# Controller_Rev_3.net
KiCad netlist of a schematic drawn in EAGLE
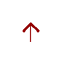
[diagram p0: schematic, sheet 1, part 1 of 3]
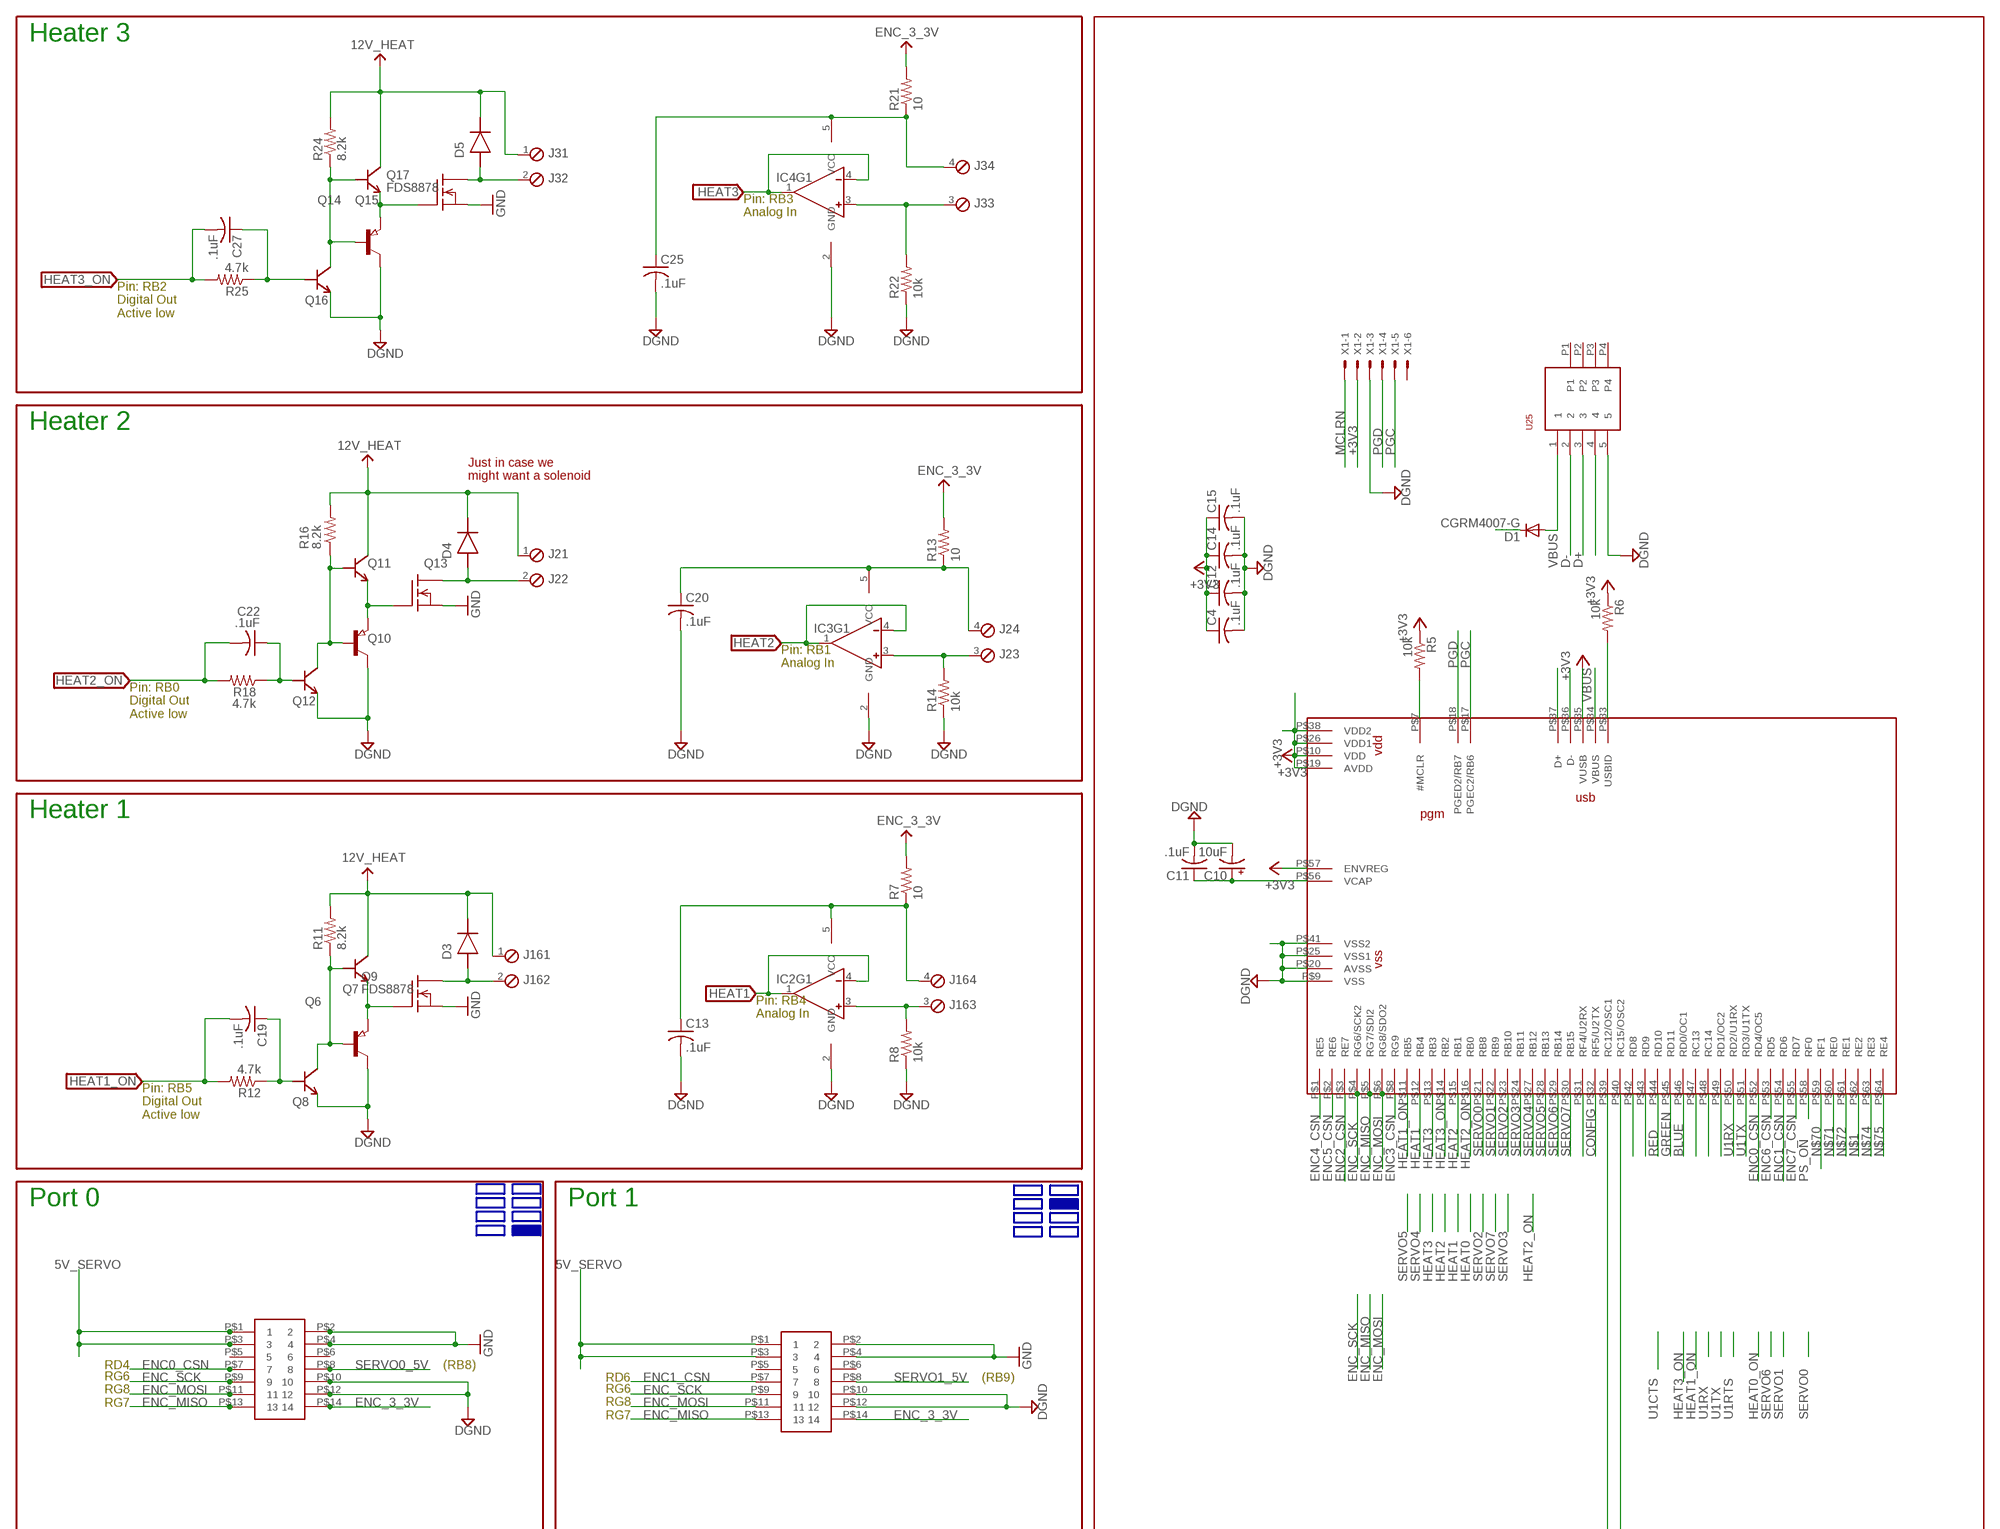
[diagram p1: schematic, sheet 1, part 2 of 3]
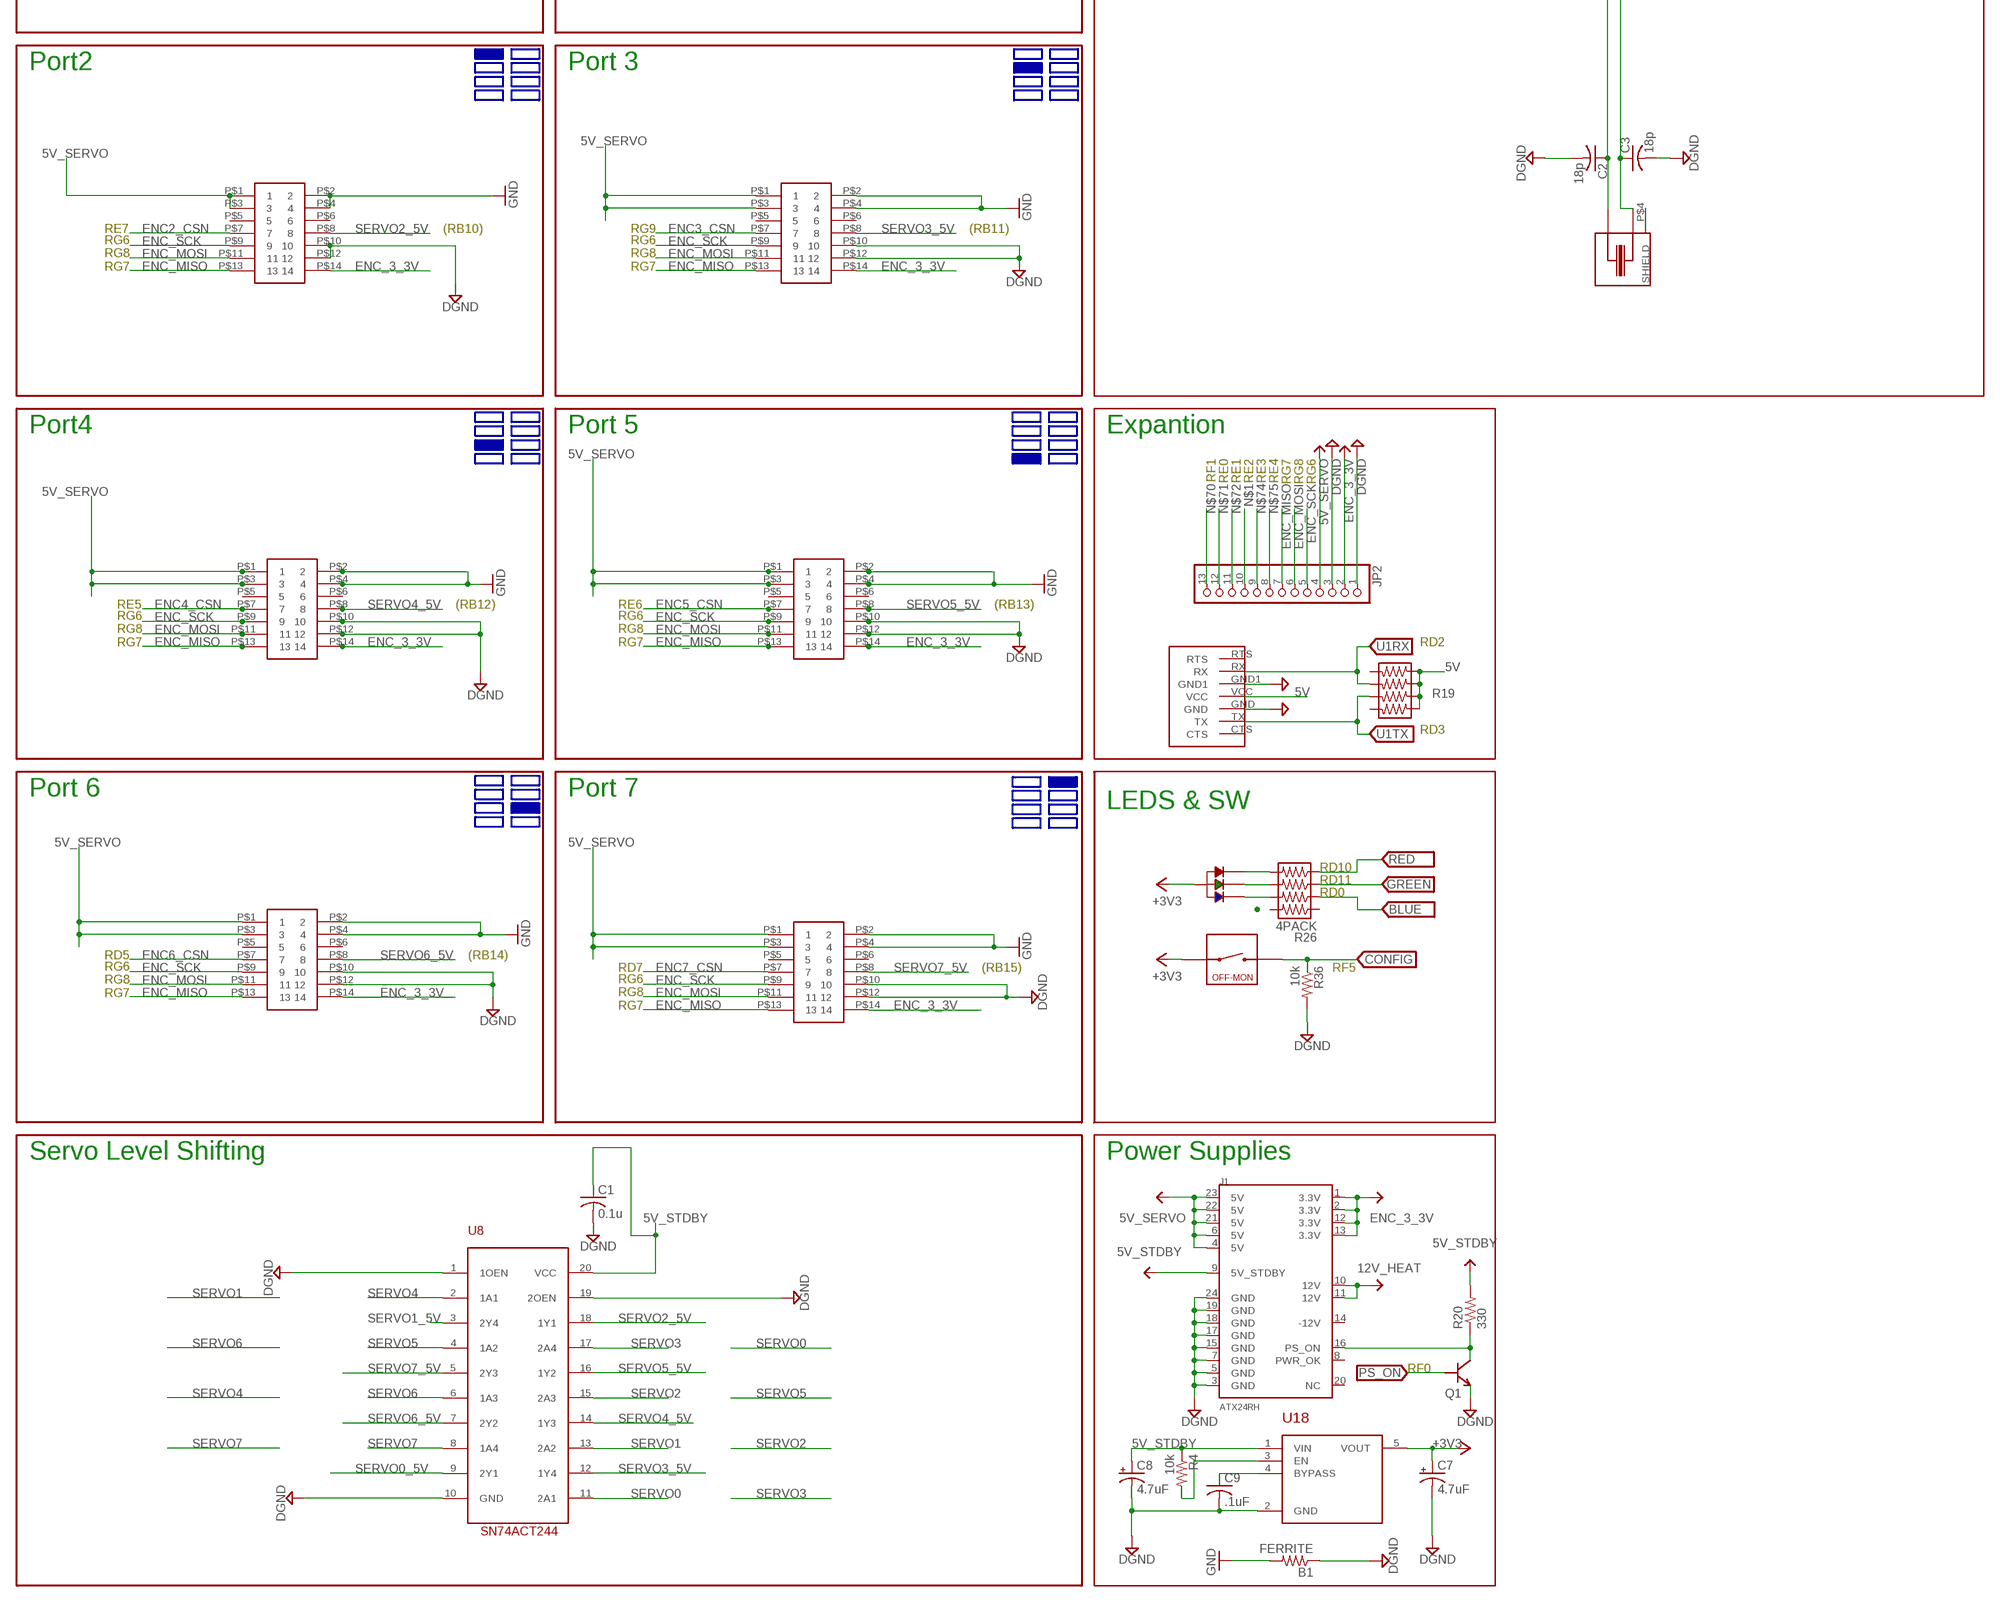
[diagram p2: schematic, sheet 1, part 3 of 3]

(export (version "E")
  (design (tool "Eeschema 10.0.6"))
  (components
    (comp (ref "B1")
      (value "FERRITE")
      (footprint "eagle-import:R0603")
      (libsource (lib "eagle-import") (part "R-US_R0603"))
    )
    (comp (ref "C1")
      (value "0.1u")
      (footprint "eagle-import:C0402")
      (libsource (lib "eagle-import") (part "resistor_C-USC0402"))
    )
    (comp (ref "C2")
      (value "18p")
      (footprint "eagle-import:C0603")
      (libsource (lib "eagle-import") (part "C-USC0603"))
    )
    (comp (ref "C3")
      (value "18p")
      (footprint "eagle-import:C0603")
      (libsource (lib "eagle-import") (part "C-USC0603"))
    )
    (comp (ref "C4")
      (value ".1uF")
      (footprint "eagle-import:C0603")
      (libsource (lib "eagle-import") (part "C-USC0603"))
    )
    (comp (ref "C7")
      (value "4.7uF")
      (footprint "eagle-import:R_2012-12R")
      (libsource (lib "eagle-import") (part "CPOL-USR/2012-12R"))
    )
    (comp (ref "C8")
      (value "4.7uF")
      (footprint "eagle-import:R_2012-12R")
      (libsource (lib "eagle-import") (part "CPOL-USR/2012-12R"))
    )
    (comp (ref "C9")
      (value ".1uF")
      (footprint "eagle-import:C0402")
      (libsource (lib "eagle-import") (part "C-USC0402"))
    )
    (comp (ref "C10")
      (value "10uF")
      (footprint "eagle-import:R_2012-12R")
      (libsource (lib "eagle-import") (part "CPOL-USR/2012-12R"))
    )
    (comp (ref "C11")
      (value ".1uF")
      (footprint "eagle-import:C0603")
      (libsource (lib "eagle-import") (part "C-USC0603"))
    )
    (comp (ref "C12")
      (value ".1uF")
      (footprint "eagle-import:C0603")
      (libsource (lib "eagle-import") (part "C-USC0603"))
    )
    (comp (ref "C13")
      (value ".1uF")
      (footprint "eagle-import:C0603")
      (libsource (lib "eagle-import") (part "C-USC0603"))
    )
    (comp (ref "C14")
      (value ".1uF")
      (footprint "eagle-import:C0603")
      (libsource (lib "eagle-import") (part "C-USC0603"))
    )
    (comp (ref "C15")
      (value ".1uF")
      (footprint "eagle-import:C0603")
      (libsource (lib "eagle-import") (part "C-USC0603"))
    )
    (comp (ref "C19")
      (value ".1uF")
      (footprint "eagle-import:C0603")
      (libsource (lib "eagle-import") (part "C-USC0603"))
    )
    (comp (ref "C20")
      (value ".1uF")
      (footprint "eagle-import:C0603")
      (libsource (lib "eagle-import") (part "C-USC0603"))
    )
    (comp (ref "C22")
      (value ".1uF")
      (footprint "eagle-import:C0603")
      (libsource (lib "eagle-import") (part "C-USC0603"))
    )
    (comp (ref "C25")
      (value ".1uF")
      (footprint "eagle-import:C0603")
      (libsource (lib "eagle-import") (part "C-USC0603"))
    )
    (comp (ref "C27")
      (value ".1uF")
      (footprint "eagle-import:C0603")
      (libsource (lib "eagle-import") (part "C-USC0603"))
    )
    (comp (ref "D1")
      (value "CGRM4007-G")
      (footprint "eagle-import:SOD-123_MINI-SMA")
      (libsource (lib "eagle-import") (part "CGRM400-G7"))
    )
    (comp (ref "D3")
      (value "DISCRETE_DIODESMA")
      (footprint "eagle-import:DISCRETE_SMA")
      (libsource (lib "eagle-import") (part "DISCRETE_DIODESMA"))
    )
    (comp (ref "D4")
      (value "DISCRETE_DIODESMA")
      (footprint "eagle-import:DISCRETE_SMA")
      (libsource (lib "eagle-import") (part "DISCRETE_DIODESMA"))
    )
    (comp (ref "D5")
      (value "DISCRETE_DIODESMA")
      (footprint "eagle-import:DISCRETE_SMA")
      (libsource (lib "eagle-import") (part "DISCRETE_DIODESMA"))
    )
    (comp (ref "IC2")
      (value "MICROCHIP_MCP6001-LT")
      (footprint "eagle-import:MICROCHIP_SC70-5-LT")
      (libsource (lib "eagle-import") (part "MICROCHIP_MCP6001-LT"))
    )
    (comp (ref "IC3")
      (value "MICROCHIP_MCP6001-LT")
      (footprint "eagle-import:MICROCHIP_SC70-5-LT")
      (libsource (lib "eagle-import") (part "MICROCHIP_MCP6001-LT"))
    )
    (comp (ref "IC4")
      (value "MICROCHIP_MCP6001-LT")
      (footprint "eagle-import:MICROCHIP_SC70-5-LT")
      (libsource (lib "eagle-import") (part "MICROCHIP_MCP6001-LT"))
    )
    (comp (ref "J1")
      (value "ATX24RH")
      (footprint "eagle-import:ATX24_RIGHT_ANGLE")
      (libsource (lib "eagle-import") (part "ATX24RH"))
    )
    (comp (ref "J2")
      (value "OSTVN04A150")
      (footprint "eagle-import:4POL254")
      (libsource (lib "eagle-import") (part "OSTVN04A150"))
    )
    (comp (ref "J3")
      (value "OSTVN04A150")
      (footprint "eagle-import:4POL254")
      (libsource (lib "eagle-import") (part "OSTVN04A150"))
    )
    (comp (ref "J10")
      (value "WASP7PIN")
      (footprint "eagle-import:WASP7PIN")
      (libsource (lib "eagle-import") (part "WASP7PIN"))
    )
    (comp (ref "J16")
      (value "OSTVN04A150")
      (footprint "eagle-import:4POL254")
      (libsource (lib "eagle-import") (part "OSTVN04A150"))
    )
    (comp (ref "JP2")
      (value "PINHD-1X13_BIG")
      (footprint "eagle-import:1X13-BIG")
      (libsource (lib "eagle-import") (part "PINHD-1X13_BIG"))
    )
    (comp (ref "Q1")
      (value "DISCRETE_MMBT3904LT1G")
      (footprint "eagle-import:DISCRETE_SOT23")
      (libsource (lib "eagle-import") (part "DISCRETE_MMBT3904LT1G"))
    )
    (comp (ref "Q6")
      (value "PNP-TRANSISTOR_SOT23")
      (footprint "eagle-import:SOT23")
      (libsource (lib "eagle-import") (part "PNP-TRANSISTOR_SOT23"))
    )
    (comp (ref "Q7")
      (value "DISCRETE_MMBT3904LT1G")
      (footprint "eagle-import:DISCRETE_SOT23")
      (libsource (lib "eagle-import") (part "DISCRETE_MMBT3904LT1G"))
    )
    (comp (ref "Q8")
      (value "DISCRETE_MMBT3904LT1G")
      (footprint "eagle-import:DISCRETE_SOT23")
      (libsource (lib "eagle-import") (part "DISCRETE_MMBT3904LT1G"))
    )
    (comp (ref "Q9")
      (value "FDS8878")
      (footprint "eagle-import:SO-8")
      (libsource (lib "eagle-import") (part "FDS5680"))
    )
    (comp (ref "Q10")
      (value "PNP-TRANSISTOR_SOT23")
      (footprint "eagle-import:SOT23")
      (libsource (lib "eagle-import") (part "PNP-TRANSISTOR_SOT23"))
    )
    (comp (ref "Q11")
      (value "DISCRETE_MMBT3904LT1G")
      (footprint "eagle-import:DISCRETE_SOT23")
      (libsource (lib "eagle-import") (part "DISCRETE_MMBT3904LT1G"))
    )
    (comp (ref "Q12")
      (value "DISCRETE_MMBT3904LT1G")
      (footprint "eagle-import:DISCRETE_SOT23")
      (libsource (lib "eagle-import") (part "DISCRETE_MMBT3904LT1G"))
    )
    (comp (ref "Q13")
      (value "FDS8878")
      (footprint "eagle-import:SO-8")
      (libsource (lib "eagle-import") (part "FDS5680"))
    )
    (comp (ref "Q14")
      (value "PNP-TRANSISTOR_SOT23")
      (footprint "eagle-import:SOT23")
      (libsource (lib "eagle-import") (part "PNP-TRANSISTOR_SOT23"))
    )
    (comp (ref "Q15")
      (value "DISCRETE_MMBT3904LT1G")
      (footprint "eagle-import:DISCRETE_SOT23")
      (libsource (lib "eagle-import") (part "DISCRETE_MMBT3904LT1G"))
    )
    (comp (ref "Q16")
      (value "DISCRETE_MMBT3904LT1G")
      (footprint "eagle-import:DISCRETE_SOT23")
      (libsource (lib "eagle-import") (part "DISCRETE_MMBT3904LT1G"))
    )
    (comp (ref "Q17")
      (value "FDS8878")
      (footprint "eagle-import:SO-8")
      (libsource (lib "eagle-import") (part "FDS5680"))
    )
    (comp (ref "R4")
      (value "10k")
      (footprint "eagle-import:R0402")
      (libsource (lib "eagle-import") (part "R-US_R0402"))
    )
    (comp (ref "R5")
      (value "10k")
      (footprint "eagle-import:R0603")
      (libsource (lib "eagle-import") (part "R-US_R0603"))
    )
    (comp (ref "R6")
      (value "10k")
      (footprint "eagle-import:R0603")
      (libsource (lib "eagle-import") (part "R-US_R0603"))
    )
    (comp (ref "R7")
      (value "10")
      (footprint "eagle-import:R0603")
      (libsource (lib "eagle-import") (part "R-US_R0603"))
    )
    (comp (ref "R8")
      (value "10k")
      (footprint "eagle-import:R0603")
      (libsource (lib "eagle-import") (part "R-US_R0603"))
    )
    (comp (ref "R11")
      (value "8.2k")
      (footprint "eagle-import:R0603")
      (libsource (lib "eagle-import") (part "R-US_R0603"))
    )
    (comp (ref "R12")
      (value "4.7k")
      (footprint "eagle-import:R0603")
      (libsource (lib "eagle-import") (part "R-US_R0603"))
    )
    (comp (ref "R13")
      (value "10")
      (footprint "eagle-import:R0603")
      (libsource (lib "eagle-import") (part "R-US_R0603"))
    )
    (comp (ref "R14")
      (value "10k")
      (footprint "eagle-import:R0603")
      (libsource (lib "eagle-import") (part "R-US_R0603"))
    )
    (comp (ref "R16")
      (value "8.2k")
      (footprint "eagle-import:R0603")
      (libsource (lib "eagle-import") (part "R-US_R0603"))
    )
    (comp (ref "R18")
      (value "4.7k")
      (footprint "eagle-import:R0603")
      (libsource (lib "eagle-import") (part "R-US_R0603"))
    )
    (comp (ref "R19")
      (value "4PACK")
      (footprint "eagle-import:4PACK_0603")
      (libsource (lib "eagle-import") (part "4PACK"))
    )
    (comp (ref "R20")
      (value "330")
      (footprint "eagle-import:R0603")
      (libsource (lib "eagle-import") (part "R-US_R0603"))
    )
    (comp (ref "R21")
      (value "10")
      (footprint "eagle-import:R0603")
      (libsource (lib "eagle-import") (part "R-US_R0603"))
    )
    (comp (ref "R22")
      (value "10k")
      (footprint "eagle-import:R0603")
      (libsource (lib "eagle-import") (part "R-US_R0603"))
    )
    (comp (ref "R24")
      (value "8.2k")
      (footprint "eagle-import:R0603")
      (libsource (lib "eagle-import") (part "R-US_R0603"))
    )
    (comp (ref "R25")
      (value "4.7k")
      (footprint "eagle-import:R0603")
      (libsource (lib "eagle-import") (part "R-US_R0603"))
    )
    (comp (ref "R26")
      (value "4PACK")
      (footprint "eagle-import:4PACK_0603")
      (libsource (lib "eagle-import") (part "4PACK"))
    )
    (comp (ref "R36")
      (value "10k")
      (footprint "eagle-import:R0603")
      (libsource (lib "eagle-import") (part "R-US_R0603"))
    )
    (comp (ref "SW3")
      (value "SPST")
      (footprint "eagle-import:B3U-1000P")
      (libsource (lib "eagle-import") (part "SPST"))
    )
    (comp (ref "U$1")
      (value "SBH11-NBPC-D07-SM-BK")
      (footprint "eagle-import:SBH11-NBPC-D07-SM-BK")
      (libsource (lib "eagle-import") (part "SBH11-NBPC-D07-SM-BK"))
    )
    (comp (ref "U$2")
      (value "SBH11-NBPC-D07-SM-BK")
      (footprint "eagle-import:SBH11-NBPC-D07-SM-BK")
      (libsource (lib "eagle-import") (part "SBH11-NBPC-D07-SM-BK"))
    )
    (comp (ref "U$3")
      (value "SBH11-NBPC-D07-SM-BK")
      (footprint "eagle-import:SBH11-NBPC-D07-SM-BK")
      (libsource (lib "eagle-import") (part "SBH11-NBPC-D07-SM-BK"))
    )
    (comp (ref "U$4")
      (value "SBH11-NBPC-D07-SM-BK")
      (footprint "eagle-import:SBH11-NBPC-D07-SM-BK")
      (libsource (lib "eagle-import") (part "SBH11-NBPC-D07-SM-BK"))
    )
    (comp (ref "U$5")
      (value "SBH11-NBPC-D07-SM-BK")
      (footprint "eagle-import:SBH11-NBPC-D07-SM-BK")
      (libsource (lib "eagle-import") (part "SBH11-NBPC-D07-SM-BK"))
    )
    (comp (ref "U$6")
      (value "SBH11-NBPC-D07-SM-BK")
      (footprint "eagle-import:SBH11-NBPC-D07-SM-BK")
      (libsource (lib "eagle-import") (part "SBH11-NBPC-D07-SM-BK"))
    )
    (comp (ref "U$7")
      (value "SBH11-NBPC-D07-SM-BK")
      (footprint "eagle-import:SBH11-NBPC-D07-SM-BK")
      (libsource (lib "eagle-import") (part "SBH11-NBPC-D07-SM-BK"))
    )
    (comp (ref "U$8")
      (value "SBH11-NBPC-D07-SM-BK")
      (footprint "eagle-import:SBH11-NBPC-D07-SM-BK")
      (libsource (lib "eagle-import") (part "SBH11-NBPC-D07-SM-BK"))
    )
    (comp (ref "U1")
      (value "TRI-LED-SMD")
      (footprint "eagle-import:TRI_LED_SMD")
      (libsource (lib "eagle-import") (part "TRI-LED-SMD"))
    )
    (comp (ref "U3")
      (value "PIC32-64TQFP64-2")
      (footprint "eagle-import:TQFP64-2")
      (libsource (lib "eagle-import") (part "PIC32-64TQFP64-2"))
    )
    (comp (ref "U8")
      (value "SN74ACT244")
      (footprint "eagle-import:20-SOIC")
      (libsource (lib "eagle-import") (part "SN74ACT244"))
    )
    (comp (ref "U18")
      (value "LDS3985XX33")
      (footprint "eagle-import:SOT23-5")
      (libsource (lib "eagle-import") (part "LDS3985XX33"))
    )
    (comp (ref "U25")
      (value "1734035-1_USB")
      (footprint "eagle-import:1734035-1_1734035")
      (libsource (lib "eagle-import") (part "1734035-1_USB"))
    )
    (comp (ref "X1")
      (value "22-23-2061")
      (footprint "eagle-import:22-23-2061")
      (fields (field (name "MF") "MOLEX"))
      (libsource (lib "eagle-import") (part "22-23-2061"))
    )
    (comp (ref "X2")
      (value "CMR3XXT")
      (footprint "eagle-import:CMR309T")
      (libsource (lib "eagle-import") (part "CMR3XXT"))
    )
  )
  (nets
    (net (code "2") (name "+3V3") (class "Default")
      (node (ref "C12") (pin "1") (pinfunction "1_1") (pintype "passive"))
      (node (ref "C14") (pin "1") (pinfunction "1_1") (pintype "passive"))
      (node (ref "C15") (pin "1") (pinfunction "1_1") (pintype "passive"))
      (node (ref "C4") (pin "1") (pinfunction "1_1") (pintype "passive"))
      (node (ref "C7") (pin "+") (pinfunction "+_+") (pintype "passive"))
      (node (ref "R5") (pin "1") (pinfunction "1_1") (pintype "passive"))
      (node (ref "R6") (pin "1") (pinfunction "1_1") (pintype "passive"))
      (node (ref "SW3") (pin "P$1") (pinfunction "P$1_P$1") (pintype "bidirectional"))
      (node (ref "U1") (pin "COMM-A") (pinfunction "COMM-A_COMM-A") (pintype "bidirectional"))
      (node (ref "U18") (pin "5") (pinfunction "VOUT_5") (pintype "bidirectional"))
      (node (ref "U3") (pin "P$10") (pinfunction "VDD_P$10") (pintype "bidirectional"))
      (node (ref "U3") (pin "P$19") (pinfunction "AVDD_P$19") (pintype "bidirectional"))
      (node (ref "U3") (pin "P$26") (pinfunction "VDD1_P$26") (pintype "bidirectional"))
      (node (ref "U3") (pin "P$35") (pinfunction "VUSB_P$35") (pintype "bidirectional"))
      (node (ref "U3") (pin "P$38") (pinfunction "VDD2_P$38") (pintype "bidirectional"))
      (node (ref "U3") (pin "P$57") (pinfunction "ENVREG_P$57") (pintype "bidirectional"))
      (node (ref "X1") (pin "2") (pinfunction "S_2") (pintype "passive"))
    )
    (net (code "3") (name "/5V") (class "Default")
      (node (ref "J10") (pin "VCC") (pinfunction "VCC_VCC") (pintype "bidirectional"))
      (node (ref "R19") (pin "R1B") (pinfunction "R1B_R1B") (pintype "passive"))
      (node (ref "R19") (pin "R2B") (pinfunction "R2B_R2B") (pintype "passive"))
      (node (ref "R19") (pin "R3B") (pinfunction "R3B_R3B") (pintype "passive"))
      (node (ref "R19") (pin "R4B") (pinfunction "R4B_R4B") (pintype "passive"))
    )
    (net (code "4") (name "/5V_SERVO") (class "Default")
      (node (ref "J1") (pin "21") (pinfunction "5V_21") (pintype "bidirectional"))
      (node (ref "J1") (pin "22") (pinfunction "5V_22") (pintype "bidirectional"))
      (node (ref "J1") (pin "23") (pinfunction "5V_23") (pintype "bidirectional"))
      (node (ref "J1") (pin "4") (pinfunction "5V_4") (pintype "bidirectional"))
      (node (ref "J1") (pin "6") (pinfunction "5V_6") (pintype "bidirectional"))
      (node (ref "JP2") (pin "4") (pinfunction "4_4") (pintype "passive"))
      (node (ref "U$1") (pin "P$1") (pinfunction "1_P$1") (pintype "bidirectional"))
      (node (ref "U$1") (pin "P$3") (pinfunction "3_P$3") (pintype "bidirectional"))
      (node (ref "U$2") (pin "P$1") (pinfunction "1_P$1") (pintype "bidirectional"))
      (node (ref "U$2") (pin "P$3") (pinfunction "3_P$3") (pintype "bidirectional"))
      (node (ref "U$3") (pin "P$1") (pinfunction "1_P$1") (pintype "bidirectional"))
      (node (ref "U$3") (pin "P$3") (pinfunction "3_P$3") (pintype "bidirectional"))
      (node (ref "U$4") (pin "P$1") (pinfunction "1_P$1") (pintype "bidirectional"))
      (node (ref "U$4") (pin "P$3") (pinfunction "3_P$3") (pintype "bidirectional"))
      (node (ref "U$5") (pin "P$1") (pinfunction "1_P$1") (pintype "bidirectional"))
      (node (ref "U$5") (pin "P$3") (pinfunction "3_P$3") (pintype "bidirectional"))
      (node (ref "U$6") (pin "P$1") (pinfunction "1_P$1") (pintype "bidirectional"))
      (node (ref "U$6") (pin "P$3") (pinfunction "3_P$3") (pintype "bidirectional"))
      (node (ref "U$7") (pin "P$1") (pinfunction "1_P$1") (pintype "bidirectional"))
      (node (ref "U$7") (pin "P$3") (pinfunction "3_P$3") (pintype "bidirectional"))
      (node (ref "U$8") (pin "P$1") (pinfunction "1_P$1") (pintype "bidirectional"))
      (node (ref "U$8") (pin "P$3") (pinfunction "3_P$3") (pintype "bidirectional"))
    )
    (net (code "5") (name "/5V_STDBY") (class "Default")
      (node (ref "C1") (pin "1") (pinfunction "1_1") (pintype "passive"))
      (node (ref "C8") (pin "+") (pinfunction "+_+") (pintype "passive"))
      (node (ref "D1") (pin "C") (pinfunction "C_C") (pintype "passive"))
      (node (ref "J1") (pin "9") (pinfunction "5V_STDBY_9") (pintype "bidirectional"))
      (node (ref "R20") (pin "2") (pinfunction "2_2") (pintype "passive"))
      (node (ref "R4") (pin "1") (pinfunction "1_1") (pintype "passive"))
      (node (ref "U18") (pin "1") (pinfunction "VIN_1") (pintype "bidirectional"))
      (node (ref "U8") (pin "20") (pinfunction "VCC_20") (pintype "bidirectional"))
    )
    (net (code "6") (name "/12V_HEAT") (class "Default")
      (node (ref "D3") (pin "C") (pinfunction "C_C") (pintype "bidirectional"))
      (node (ref "D4") (pin "C") (pinfunction "C_C") (pintype "bidirectional"))
      (node (ref "D5") (pin "C") (pinfunction "C_C") (pintype "bidirectional"))
      (node (ref "J1") (pin "10") (pinfunction "12V_10") (pintype "bidirectional"))
      (node (ref "J1") (pin "11") (pinfunction "12V_11") (pintype "bidirectional"))
      (node (ref "J16") (pin "1") (pinfunction "1_1") (pintype "passive"))
      (node (ref "J2") (pin "1") (pinfunction "1_1") (pintype "passive"))
      (node (ref "J3") (pin "1") (pinfunction "1_1") (pintype "passive"))
      (node (ref "Q11") (pin "3") (pinfunction "C_3") (pintype "bidirectional"))
      (node (ref "Q15") (pin "3") (pinfunction "C_3") (pintype "bidirectional"))
      (node (ref "Q7") (pin "3") (pinfunction "C_3") (pintype "bidirectional"))
      (node (ref "R11") (pin "2") (pinfunction "2_2") (pintype "passive"))
      (node (ref "R16") (pin "2") (pinfunction "2_2") (pintype "passive"))
      (node (ref "R24") (pin "2") (pinfunction "2_2") (pintype "passive"))
    )
    (net (code "7") (name "/BLUE") (class "Default")
      (node (ref "R26") (pin "R2B") (pinfunction "R2B_R2B") (pintype "passive"))
      (node (ref "U3") (pin "P$46") (pinfunction "RD0/OC1_P$46") (pintype "bidirectional"))
    )
    (net (code "8") (name "/CONFIG") (class "Default")
      (node (ref "R36") (pin "1") (pinfunction "1_1") (pintype "passive"))
      (node (ref "SW3") (pin "P$3") (pinfunction "P$2_P$3") (pintype "bidirectional"))
      (node (ref "U3") (pin "P$32") (pinfunction "RF5/U2TX_P$32") (pintype "bidirectional"))
    )
    (net (code "9") (name "/D+") (class "Default")
      (node (ref "U25") (pin "3") (pinfunction "3_3") (pintype "bidirectional"))
      (node (ref "U3") (pin "P$37") (pinfunction "D+_P$37") (pintype "bidirectional"))
    )
    (net (code "10") (name "/D-") (class "Default")
      (node (ref "U25") (pin "2") (pinfunction "2_2") (pintype "bidirectional"))
      (node (ref "U3") (pin "P$36") (pinfunction "D-_P$36") (pintype "bidirectional"))
    )
    (net (code "11") (name "/ENC0_CSN") (class "Default")
      (node (ref "U$8") (pin "P$7") (pinfunction "7_P$7") (pintype "bidirectional"))
      (node (ref "U3") (pin "P$52") (pinfunction "RD4/OC5_P$52") (pintype "bidirectional"))
    )
    (net (code "12") (name "/ENC1_CSN") (class "Default")
      (node (ref "U$6") (pin "P$7") (pinfunction "7_P$7") (pintype "bidirectional"))
      (node (ref "U3") (pin "P$54") (pinfunction "RD6_P$54") (pintype "bidirectional"))
    )
    (net (code "13") (name "/ENC2_CSN") (class "Default")
      (node (ref "U$1") (pin "P$7") (pinfunction "7_P$7") (pintype "bidirectional"))
      (node (ref "U3") (pin "P$3") (pinfunction "RE7_P$3") (pintype "bidirectional"))
    )
    (net (code "14") (name "/ENC3_CSN") (class "Default")
      (node (ref "U$2") (pin "P$7") (pinfunction "7_P$7") (pintype "bidirectional"))
      (node (ref "U3") (pin "P$8") (pinfunction "RG9_P$8") (pintype "bidirectional"))
    )
    (net (code "15") (name "/ENC4_CSN") (class "Default")
      (node (ref "U$3") (pin "P$7") (pinfunction "7_P$7") (pintype "bidirectional"))
      (node (ref "U3") (pin "P$1") (pinfunction "RE5_P$1") (pintype "bidirectional"))
    )
    (net (code "16") (name "/ENC5_CSN") (class "Default")
      (node (ref "U$4") (pin "P$7") (pinfunction "7_P$7") (pintype "bidirectional"))
      (node (ref "U3") (pin "P$2") (pinfunction "RE6_P$2") (pintype "bidirectional"))
    )
    (net (code "17") (name "/ENC6_CSN") (class "Default")
      (node (ref "U$7") (pin "P$7") (pinfunction "7_P$7") (pintype "bidirectional"))
      (node (ref "U3") (pin "P$53") (pinfunction "RD5_P$53") (pintype "bidirectional"))
    )
    (net (code "18") (name "/ENC7_CSN") (class "Default")
      (node (ref "U$5") (pin "P$7") (pinfunction "7_P$7") (pintype "bidirectional"))
      (node (ref "U3") (pin "P$55") (pinfunction "RD7_P$55") (pintype "bidirectional"))
    )
    (net (code "19") (name "/ENC_3_3V") (class "Default")
      (node (ref "J1") (pin "1") (pinfunction "3.3V_1") (pintype "bidirectional"))
      (node (ref "J1") (pin "12") (pinfunction "3.3V_12") (pintype "bidirectional"))
      (node (ref "J1") (pin "13") (pinfunction "3.3V_13") (pintype "bidirectional"))
      (node (ref "J1") (pin "2") (pinfunction "3.3V_2") (pintype "bidirectional"))
      (node (ref "JP2") (pin "2") (pinfunction "2_2") (pintype "passive"))
      (node (ref "R13") (pin "2") (pinfunction "2_2") (pintype "passive"))
      (node (ref "R21") (pin "2") (pinfunction "2_2") (pintype "passive"))
      (node (ref "R7") (pin "2") (pinfunction "2_2") (pintype "passive"))
      (node (ref "U$1") (pin "P$14") (pinfunction "14_P$14") (pintype "bidirectional"))
      (node (ref "U$2") (pin "P$14") (pinfunction "14_P$14") (pintype "bidirectional"))
      (node (ref "U$3") (pin "P$14") (pinfunction "14_P$14") (pintype "bidirectional"))
      (node (ref "U$4") (pin "P$14") (pinfunction "14_P$14") (pintype "bidirectional"))
      (node (ref "U$5") (pin "P$14") (pinfunction "14_P$14") (pintype "bidirectional"))
      (node (ref "U$6") (pin "P$14") (pinfunction "14_P$14") (pintype "bidirectional"))
      (node (ref "U$7") (pin "P$14") (pinfunction "14_P$14") (pintype "bidirectional"))
      (node (ref "U$8") (pin "P$14") (pinfunction "14_P$14") (pintype "bidirectional"))
    )
    (net (code "20") (name "/ENC_MISO") (class "Default")
      (node (ref "JP2") (pin "7") (pinfunction "7_7") (pintype "passive"))
      (node (ref "U$1") (pin "P$13") (pinfunction "13_P$13") (pintype "bidirectional"))
      (node (ref "U$2") (pin "P$13") (pinfunction "13_P$13") (pintype "bidirectional"))
      (node (ref "U$3") (pin "P$13") (pinfunction "13_P$13") (pintype "bidirectional"))
      (node (ref "U$4") (pin "P$13") (pinfunction "13_P$13") (pintype "bidirectional"))
      (node (ref "U$5") (pin "P$13") (pinfunction "13_P$13") (pintype "bidirectional"))
      (node (ref "U$6") (pin "P$13") (pinfunction "13_P$13") (pintype "bidirectional"))
      (node (ref "U$7") (pin "P$13") (pinfunction "13_P$13") (pintype "bidirectional"))
      (node (ref "U$8") (pin "P$13") (pinfunction "13_P$13") (pintype "bidirectional"))
      (node (ref "U3") (pin "P$5") (pinfunction "RG7/SDI2_P$5") (pintype "bidirectional"))
    )
    (net (code "21") (name "/ENC_MOSI") (class "Default")
      (node (ref "JP2") (pin "6") (pinfunction "6_6") (pintype "passive"))
      (node (ref "U$1") (pin "P$11") (pinfunction "11_P$11") (pintype "bidirectional"))
      (node (ref "U$2") (pin "P$11") (pinfunction "11_P$11") (pintype "bidirectional"))
      (node (ref "U$3") (pin "P$11") (pinfunction "11_P$11") (pintype "bidirectional"))
      (node (ref "U$4") (pin "P$11") (pinfunction "11_P$11") (pintype "bidirectional"))
      (node (ref "U$5") (pin "P$11") (pinfunction "11_P$11") (pintype "bidirectional"))
      (node (ref "U$6") (pin "P$11") (pinfunction "11_P$11") (pintype "bidirectional"))
      (node (ref "U$7") (pin "P$11") (pinfunction "11_P$11") (pintype "bidirectional"))
      (node (ref "U$8") (pin "P$11") (pinfunction "11_P$11") (pintype "bidirectional"))
      (node (ref "U3") (pin "P$6") (pinfunction "RG8/SDO2_P$6") (pintype "bidirectional"))
    )
    (net (code "22") (name "/ENC_SCK") (class "Default")
      (node (ref "JP2") (pin "5") (pinfunction "5_5") (pintype "passive"))
      (node (ref "U$1") (pin "P$9") (pinfunction "9_P$9") (pintype "bidirectional"))
      (node (ref "U$2") (pin "P$9") (pinfunction "9_P$9") (pintype "bidirectional"))
      (node (ref "U$3") (pin "P$9") (pinfunction "9_P$9") (pintype "bidirectional"))
      (node (ref "U$4") (pin "P$9") (pinfunction "9_P$9") (pintype "bidirectional"))
      (node (ref "U$5") (pin "P$9") (pinfunction "9_P$9") (pintype "bidirectional"))
      (node (ref "U$6") (pin "P$9") (pinfunction "9_P$9") (pintype "bidirectional"))
      (node (ref "U$7") (pin "P$9") (pinfunction "9_P$9") (pintype "bidirectional"))
      (node (ref "U$8") (pin "P$9") (pinfunction "9_P$9") (pintype "bidirectional"))
      (node (ref "U3") (pin "P$4") (pinfunction "RG6/SCK2_P$4") (pintype "bidirectional"))
    )
    (net (code "23") (name "/GREEN") (class "Default")
      (node (ref "R26") (pin "R3B") (pinfunction "R3B_R3B") (pintype "passive"))
      (node (ref "U3") (pin "P$45") (pinfunction "RD11_P$45") (pintype "bidirectional"))
    )
    (net (code "26") (name "/HEAT1") (class "Default")
      (node (ref "IC2") (pin "1") (pinfunction "OUT_1") (pintype "output"))
      (node (ref "IC2") (pin "4") (pinfunction "IN-_4") (pintype "input"))
      (node (ref "U3") (pin "P$12") (pinfunction "RB4_P$12") (pintype "bidirectional"))
    )
    (net (code "27") (name "/HEAT1_ON") (class "Default")
      (node (ref "C19") (pin "2") (pinfunction "2_2") (pintype "passive"))
      (node (ref "R12") (pin "2") (pinfunction "2_2") (pintype "passive"))
      (node (ref "U3") (pin "P$11") (pinfunction "RB5_P$11") (pintype "bidirectional"))
    )
    (net (code "28") (name "/HEAT2") (class "Default")
      (node (ref "IC3") (pin "1") (pinfunction "OUT_1") (pintype "output"))
      (node (ref "IC3") (pin "4") (pinfunction "IN-_4") (pintype "input"))
      (node (ref "U3") (pin "P$15") (pinfunction "RB1_P$15") (pintype "bidirectional"))
    )
    (net (code "29") (name "/HEAT2_ON") (class "Default")
      (node (ref "C22") (pin "2") (pinfunction "2_2") (pintype "passive"))
      (node (ref "R18") (pin "2") (pinfunction "2_2") (pintype "passive"))
      (node (ref "U3") (pin "P$16") (pinfunction "RB0_P$16") (pintype "bidirectional"))
    )
    (net (code "30") (name "/HEAT3") (class "Default")
      (node (ref "IC4") (pin "1") (pinfunction "OUT_1") (pintype "output"))
      (node (ref "IC4") (pin "4") (pinfunction "IN-_4") (pintype "input"))
      (node (ref "U3") (pin "P$13") (pinfunction "RB3_P$13") (pintype "bidirectional"))
    )
    (net (code "31") (name "/HEAT3_ON") (class "Default")
      (node (ref "C27") (pin "2") (pinfunction "2_2") (pintype "passive"))
      (node (ref "R25") (pin "2") (pinfunction "2_2") (pintype "passive"))
      (node (ref "U3") (pin "P$14") (pinfunction "RB2_P$14") (pintype "bidirectional"))
    )
    (net (code "32") (name "/MCLRN") (class "Default")
      (node (ref "R5") (pin "2") (pinfunction "2_2") (pintype "passive"))
      (node (ref "U3") (pin "P$7") (pinfunction "#MCLR_P$7") (pintype "bidirectional"))
      (node (ref "X1") (pin "1") (pinfunction "S_1") (pintype "passive"))
    )
    (net (code "33") (name "/N$1") (class "Default")
      (node (ref "JP2") (pin "10") (pinfunction "10_10") (pintype "passive"))
      (node (ref "U3") (pin "P$62") (pinfunction "RE2_P$62") (pintype "bidirectional"))
    )
    (net (code "34") (name "/N$70") (class "Default")
      (node (ref "JP2") (pin "13") (pinfunction "13_13") (pintype "passive"))
      (node (ref "U3") (pin "P$59") (pinfunction "RF1_P$59") (pintype "bidirectional"))
    )
    (net (code "35") (name "/N$71") (class "Default")
      (node (ref "JP2") (pin "12") (pinfunction "12_12") (pintype "passive"))
      (node (ref "U3") (pin "P$60") (pinfunction "RE0_P$60") (pintype "bidirectional"))
    )
    (net (code "36") (name "/N$72") (class "Default")
      (node (ref "JP2") (pin "11") (pinfunction "11_11") (pintype "passive"))
      (node (ref "U3") (pin "P$61") (pinfunction "RE1_P$61") (pintype "bidirectional"))
    )
    (net (code "37") (name "/N$74") (class "Default")
      (node (ref "JP2") (pin "9") (pinfunction "9_9") (pintype "passive"))
      (node (ref "U3") (pin "P$63") (pinfunction "RE3_P$63") (pintype "bidirectional"))
    )
    (net (code "38") (name "/N$75") (class "Default")
      (node (ref "JP2") (pin "8") (pinfunction "8_8") (pintype "passive"))
      (node (ref "U3") (pin "P$64") (pinfunction "RE4_P$64") (pintype "bidirectional"))
    )
    (net (code "39") (name "/PGC") (class "Default")
      (node (ref "U3") (pin "P$17") (pinfunction "PGEC2/RB6_P$17") (pintype "bidirectional"))
      (node (ref "X1") (pin "5") (pinfunction "S_5") (pintype "passive"))
    )
    (net (code "40") (name "/PGD") (class "Default")
      (node (ref "U3") (pin "P$18") (pinfunction "PGED2/RB7_P$18") (pintype "bidirectional"))
      (node (ref "X1") (pin "4") (pinfunction "S_4") (pintype "passive"))
    )
    (net (code "41") (name "/PS_ON") (class "Default")
      (node (ref "Q1") (pin "1") (pinfunction "B_1") (pintype "bidirectional"))
      (node (ref "U3") (pin "P$58") (pinfunction "RF0_P$58") (pintype "bidirectional"))
    )
    (net (code "42") (name "/RED") (class "Default")
      (node (ref "R26") (pin "R4B") (pinfunction "R4B_R4B") (pintype "passive"))
      (node (ref "U3") (pin "P$44") (pinfunction "RD10_P$44") (pintype "bidirectional"))
    )
    (net (code "43") (name "/SERVO0") (class "Default")
      (node (ref "U3") (pin "P$21") (pinfunction "RB8_P$21") (pintype "bidirectional"))
      (node (ref "U8") (pin "11") (pinfunction "2A1_11") (pintype "bidirectional"))
    )
    (net (code "44") (name "/SERVO0_5V") (class "Default")
      (node (ref "U$8") (pin "P$8") (pinfunction "8_P$8") (pintype "bidirectional"))
      (node (ref "U8") (pin "9") (pinfunction "2Y1_9") (pintype "bidirectional"))
    )
    (net (code "45") (name "/SERVO1") (class "Default")
      (node (ref "U3") (pin "P$22") (pinfunction "RB9_P$22") (pintype "bidirectional"))
      (node (ref "U8") (pin "13") (pinfunction "2A2_13") (pintype "bidirectional"))
    )
    (net (code "46") (name "/SERVO1_5V") (class "Default")
      (node (ref "U$6") (pin "P$8") (pinfunction "8_P$8") (pintype "bidirectional"))
      (node (ref "U8") (pin "3") (pinfunction "2Y4_3") (pintype "bidirectional"))
    )
    (net (code "47") (name "/SERVO2") (class "Default")
      (node (ref "U3") (pin "P$23") (pinfunction "RB10_P$23") (pintype "bidirectional"))
      (node (ref "U8") (pin "15") (pinfunction "2A3_15") (pintype "bidirectional"))
    )
    (net (code "48") (name "/SERVO2_5V") (class "Default")
      (node (ref "U$1") (pin "P$8") (pinfunction "8_P$8") (pintype "bidirectional"))
      (node (ref "U8") (pin "18") (pinfunction "1Y1_18") (pintype "bidirectional"))
    )
    (net (code "49") (name "/SERVO3") (class "Default")
      (node (ref "U3") (pin "P$24") (pinfunction "RB11_P$24") (pintype "bidirectional"))
      (node (ref "U8") (pin "17") (pinfunction "2A4_17") (pintype "bidirectional"))
    )
    (net (code "50") (name "/SERVO3_5V") (class "Default")
      (node (ref "U$2") (pin "P$8") (pinfunction "8_P$8") (pintype "bidirectional"))
      (node (ref "U8") (pin "12") (pinfunction "1Y4_12") (pintype "bidirectional"))
    )
    (net (code "51") (name "/SERVO4") (class "Default")
      (node (ref "U3") (pin "P$27") (pinfunction "RB12_P$27") (pintype "bidirectional"))
      (node (ref "U8") (pin "2") (pinfunction "1A1_2") (pintype "bidirectional"))
    )
    (net (code "52") (name "/SERVO4_5V") (class "Default")
      (node (ref "U$3") (pin "P$8") (pinfunction "8_P$8") (pintype "bidirectional"))
      (node (ref "U8") (pin "14") (pinfunction "1Y3_14") (pintype "bidirectional"))
    )
    (net (code "53") (name "/SERVO5") (class "Default")
      (node (ref "U3") (pin "P$28") (pinfunction "RB13_P$28") (pintype "bidirectional"))
      (node (ref "U8") (pin "4") (pinfunction "1A2_4") (pintype "bidirectional"))
    )
    (net (code "54") (name "/SERVO5_5V") (class "Default")
      (node (ref "U$4") (pin "P$8") (pinfunction "8_P$8") (pintype "bidirectional"))
      (node (ref "U8") (pin "16") (pinfunction "1Y2_16") (pintype "bidirectional"))
    )
    (net (code "55") (name "/SERVO6") (class "Default")
      (node (ref "U3") (pin "P$29") (pinfunction "RB14_P$29") (pintype "bidirectional"))
      (node (ref "U8") (pin "6") (pinfunction "1A3_6") (pintype "bidirectional"))
    )
    (net (code "56") (name "/SERVO6_5V") (class "Default")
      (node (ref "U$7") (pin "P$8") (pinfunction "8_P$8") (pintype "bidirectional"))
      (node (ref "U8") (pin "7") (pinfunction "2Y2_7") (pintype "bidirectional"))
    )
    (net (code "57") (name "/SERVO7") (class "Default")
      (node (ref "U3") (pin "P$30") (pinfunction "RB15_P$30") (pintype "bidirectional"))
      (node (ref "U8") (pin "8") (pinfunction "1A4_8") (pintype "bidirectional"))
    )
    (net (code "58") (name "/SERVO7_5V") (class "Default")
      (node (ref "U$5") (pin "P$8") (pinfunction "8_P$8") (pintype "bidirectional"))
      (node (ref "U8") (pin "5") (pinfunction "2Y3_5") (pintype "bidirectional"))
    )
    (net (code "61") (name "/U1RX") (class "Default")
      (node (ref "J10") (pin "RX") (pinfunction "RX_RX") (pintype "bidirectional"))
      (node (ref "R19") (pin "R2A") (pinfunction "R2A_R2A") (pintype "passive"))
      (node (ref "U3") (pin "P$50") (pinfunction "RD2/U1RX_P$50") (pintype "bidirectional"))
    )
    (net (code "62") (name "/U1TX") (class "Default")
      (node (ref "J10") (pin "TX") (pinfunction "TX_TX") (pintype "bidirectional"))
      (node (ref "R19") (pin "R3A") (pinfunction "R3A_R3A") (pintype "passive"))
      (node (ref "U3") (pin "P$51") (pinfunction "RD3/U1TX_P$51") (pintype "bidirectional"))
    )
    (net (code "63") (name "/USBID") (class "Default")
      (node (ref "R6") (pin "2") (pinfunction "2_2") (pintype "passive"))
      (node (ref "U25") (pin "4") (pinfunction "4_4") (pintype "bidirectional"))
      (node (ref "U3") (pin "P$33") (pinfunction "USBID_P$33") (pintype "bidirectional"))
    )
    (net (code "64") (name "/VBUS") (class "Default")
      (node (ref "D1") (pin "A") (pinfunction "A_A") (pintype "passive"))
      (node (ref "U25") (pin "1") (pinfunction "1_1") (pintype "bidirectional"))
      (node (ref "U3") (pin "P$34") (pinfunction "VBUS_P$34") (pintype "bidirectional"))
    )
    (net (code "66") (name "DGND") (class "Default")
      (node (ref "B1") (pin "1") (pinfunction "1_1") (pintype "passive"))
      (node (ref "C1") (pin "2") (pinfunction "2_2") (pintype "passive"))
      (node (ref "C10") (pin "-") (pinfunction "-_-") (pintype "passive"))
      (node (ref "C11") (pin "2") (pinfunction "2_2") (pintype "passive"))
      (node (ref "C12") (pin "2") (pinfunction "2_2") (pintype "passive"))
      (node (ref "C13") (pin "2") (pinfunction "2_2") (pintype "passive"))
      (node (ref "C14") (pin "2") (pinfunction "2_2") (pintype "passive"))
      (node (ref "C15") (pin "2") (pinfunction "2_2") (pintype "passive"))
      (node (ref "C2") (pin "2") (pinfunction "2_2") (pintype "passive"))
      (node (ref "C20") (pin "2") (pinfunction "2_2") (pintype "passive"))
      (node (ref "C25") (pin "2") (pinfunction "2_2") (pintype "passive"))
      (node (ref "C3") (pin "2") (pinfunction "2_2") (pintype "passive"))
      (node (ref "C4") (pin "2") (pinfunction "2_2") (pintype "passive"))
      (node (ref "C7") (pin "-") (pinfunction "-_-") (pintype "passive"))
      (node (ref "C8") (pin "-") (pinfunction "-_-") (pintype "passive"))
      (node (ref "C9") (pin "2") (pinfunction "2_2") (pintype "passive"))
      (node (ref "IC2") (pin "2") (pinfunction "GND_2") (pintype "bidirectional"))
      (node (ref "IC3") (pin "2") (pinfunction "GND_2") (pintype "bidirectional"))
      (node (ref "IC4") (pin "2") (pinfunction "GND_2") (pintype "bidirectional"))
      (node (ref "J1") (pin "15") (pinfunction "GND_15") (pintype "bidirectional"))
      (node (ref "J1") (pin "17") (pinfunction "GND_17") (pintype "bidirectional"))
      (node (ref "J1") (pin "18") (pinfunction "GND_18") (pintype "bidirectional"))
      (node (ref "J1") (pin "19") (pinfunction "GND_19") (pintype "bidirectional"))
      (node (ref "J1") (pin "24") (pinfunction "GND_24") (pintype "bidirectional"))
      (node (ref "J1") (pin "3") (pinfunction "GND_3") (pintype "bidirectional"))
      (node (ref "J1") (pin "5") (pinfunction "GND_5") (pintype "bidirectional"))
      (node (ref "J1") (pin "7") (pinfunction "GND_7") (pintype "bidirectional"))
      (node (ref "J10") (pin "GND") (pinfunction "GND_GND") (pintype "bidirectional"))
      (node (ref "J10") (pin "GND1") (pinfunction "GND1_GND1") (pintype "bidirectional"))
      (node (ref "JP2") (pin "1") (pinfunction "1_1") (pintype "passive"))
      (node (ref "JP2") (pin "3") (pinfunction "3_3") (pintype "passive"))
      (node (ref "Q1") (pin "2") (pinfunction "E_2") (pintype "bidirectional"))
      (node (ref "Q10") (pin "3") (pinfunction "C_3") (pintype "passive"))
      (node (ref "Q12") (pin "2") (pinfunction "E_2") (pintype "bidirectional"))
      (node (ref "Q14") (pin "3") (pinfunction "C_3") (pintype "passive"))
      (node (ref "Q16") (pin "2") (pinfunction "E_2") (pintype "bidirectional"))
      (node (ref "Q6") (pin "3") (pinfunction "C_3") (pintype "passive"))
      (node (ref "Q8") (pin "2") (pinfunction "E_2") (pintype "bidirectional"))
      (node (ref "R14") (pin "1") (pinfunction "1_1") (pintype "passive"))
      (node (ref "R22") (pin "1") (pinfunction "1_1") (pintype "passive"))
      (node (ref "R36") (pin "2") (pinfunction "2_2") (pintype "passive"))
      (node (ref "R8") (pin "1") (pinfunction "1_1") (pintype "passive"))
      (node (ref "U$1") (pin "P$10") (pinfunction "10_P$10") (pintype "bidirectional"))
      (node (ref "U$1") (pin "P$12") (pinfunction "12_P$12") (pintype "bidirectional"))
      (node (ref "U$2") (pin "P$10") (pinfunction "10_P$10") (pintype "bidirectional"))
      (node (ref "U$2") (pin "P$12") (pinfunction "12_P$12") (pintype "bidirectional"))
      (node (ref "U$3") (pin "P$10") (pinfunction "10_P$10") (pintype "bidirectional"))
      (node (ref "U$3") (pin "P$12") (pinfunction "12_P$12") (pintype "bidirectional"))
      (node (ref "U$4") (pin "P$10") (pinfunction "10_P$10") (pintype "bidirectional"))
      (node (ref "U$4") (pin "P$12") (pinfunction "12_P$12") (pintype "bidirectional"))
      (node (ref "U$5") (pin "P$10") (pinfunction "10_P$10") (pintype "bidirectional"))
      (node (ref "U$5") (pin "P$12") (pinfunction "12_P$12") (pintype "bidirectional"))
      (node (ref "U$6") (pin "P$10") (pinfunction "10_P$10") (pintype "bidirectional"))
      (node (ref "U$6") (pin "P$12") (pinfunction "12_P$12") (pintype "bidirectional"))
      (node (ref "U$7") (pin "P$10") (pinfunction "10_P$10") (pintype "bidirectional"))
      (node (ref "U$7") (pin "P$12") (pinfunction "12_P$12") (pintype "bidirectional"))
      (node (ref "U$8") (pin "P$10") (pinfunction "10_P$10") (pintype "bidirectional"))
      (node (ref "U$8") (pin "P$12") (pinfunction "12_P$12") (pintype "bidirectional"))
      (node (ref "U18") (pin "2") (pinfunction "GND_2") (pintype "bidirectional"))
      (node (ref "U25") (pin "5") (pinfunction "5_5") (pintype "bidirectional"))
      (node (ref "U3") (pin "P$20") (pinfunction "AVSS_P$20") (pintype "bidirectional"))
      (node (ref "U3") (pin "P$25") (pinfunction "VSS1_P$25") (pintype "bidirectional"))
      (node (ref "U3") (pin "P$41") (pinfunction "VSS2_P$41") (pintype "bidirectional"))
      (node (ref "U3") (pin "P$9") (pinfunction "VSS_P$9") (pintype "bidirectional"))
      (node (ref "U8") (pin "1") (pinfunction "1OEN_1") (pintype "bidirectional"))
      (node (ref "U8") (pin "10") (pinfunction "GND_10") (pintype "bidirectional"))
      (node (ref "U8") (pin "19") (pinfunction "2OEN_19") (pintype "bidirectional"))
      (node (ref "X1") (pin "3") (pinfunction "S_3") (pintype "passive"))
    )
    (net (code "67") (name "GND") (class "Default")
      (node (ref "B1") (pin "2") (pinfunction "2_2") (pintype "passive"))
      (node (ref "Q13") (pin "1") (pinfunction "S_1") (pintype "passive"))
      (node (ref "Q13") (pin "2") (pinfunction "S_2") (pintype "passive"))
      (node (ref "Q13") (pin "3") (pinfunction "S_3") (pintype "passive"))
      (node (ref "Q17") (pin "1") (pinfunction "S_1") (pintype "passive"))
      (node (ref "Q17") (pin "2") (pinfunction "S_2") (pintype "passive"))
      (node (ref "Q17") (pin "3") (pinfunction "S_3") (pintype "passive"))
      (node (ref "Q9") (pin "1") (pinfunction "S_1") (pintype "passive"))
      (node (ref "Q9") (pin "2") (pinfunction "S_2") (pintype "passive"))
      (node (ref "Q9") (pin "3") (pinfunction "S_3") (pintype "passive"))
      (node (ref "U$1") (pin "P$2") (pinfunction "2_P$2") (pintype "bidirectional"))
      (node (ref "U$1") (pin "P$4") (pinfunction "4_P$4") (pintype "bidirectional"))
      (node (ref "U$2") (pin "P$2") (pinfunction "2_P$2") (pintype "bidirectional"))
      (node (ref "U$2") (pin "P$4") (pinfunction "4_P$4") (pintype "bidirectional"))
      (node (ref "U$3") (pin "P$2") (pinfunction "2_P$2") (pintype "bidirectional"))
      (node (ref "U$3") (pin "P$4") (pinfunction "4_P$4") (pintype "bidirectional"))
      (node (ref "U$4") (pin "P$2") (pinfunction "2_P$2") (pintype "bidirectional"))
      (node (ref "U$4") (pin "P$4") (pinfunction "4_P$4") (pintype "bidirectional"))
      (node (ref "U$5") (pin "P$2") (pinfunction "2_P$2") (pintype "bidirectional"))
      (node (ref "U$5") (pin "P$4") (pinfunction "4_P$4") (pintype "bidirectional"))
      (node (ref "U$6") (pin "P$2") (pinfunction "2_P$2") (pintype "bidirectional"))
      (node (ref "U$6") (pin "P$4") (pinfunction "4_P$4") (pintype "bidirectional"))
      (node (ref "U$7") (pin "P$2") (pinfunction "2_P$2") (pintype "bidirectional"))
      (node (ref "U$7") (pin "P$4") (pinfunction "4_P$4") (pintype "bidirectional"))
      (node (ref "U$8") (pin "P$2") (pinfunction "2_P$2") (pintype "bidirectional"))
      (node (ref "U$8") (pin "P$4") (pinfunction "4_P$4") (pintype "bidirectional"))
    )
    (net (code "68") (name "Net-(IC2A-IN+)") (class "Default")
      (node (ref "IC2") (pin "3") (pinfunction "IN+_3") (pintype "input"))
      (node (ref "J16") (pin "3") (pinfunction "1_3") (pintype "passive"))
      (node (ref "R8") (pin "2") (pinfunction "2_2") (pintype "passive"))
    )
    (net (code "69") (name "Net-(IC2B-VCC)") (class "Default")
      (node (ref "C13") (pin "1") (pinfunction "1_1") (pintype "passive"))
      (node (ref "IC2") (pin "5") (pinfunction "VCC_5") (pintype "bidirectional"))
      (node (ref "J16") (pin "4") (pinfunction "1_4") (pintype "passive"))
      (node (ref "R7") (pin "1") (pinfunction "1_1") (pintype "passive"))
    )
    (net (code "70") (name "Net-(IC3A-IN+)") (class "Default")
      (node (ref "IC3") (pin "3") (pinfunction "IN+_3") (pintype "input"))
      (node (ref "J2") (pin "3") (pinfunction "1_3") (pintype "passive"))
      (node (ref "R14") (pin "2") (pinfunction "2_2") (pintype "passive"))
    )
    (net (code "71") (name "Net-(IC3B-VCC)") (class "Default")
      (node (ref "C20") (pin "1") (pinfunction "1_1") (pintype "passive"))
      (node (ref "IC3") (pin "5") (pinfunction "VCC_5") (pintype "bidirectional"))
      (node (ref "J2") (pin "4") (pinfunction "1_4") (pintype "passive"))
      (node (ref "R13") (pin "1") (pinfunction "1_1") (pintype "passive"))
    )
    (net (code "72") (name "Net-(IC4A-IN+)") (class "Default")
      (node (ref "IC4") (pin "3") (pinfunction "IN+_3") (pintype "input"))
      (node (ref "J3") (pin "3") (pinfunction "1_3") (pintype "passive"))
      (node (ref "R22") (pin "2") (pinfunction "2_2") (pintype "passive"))
    )
    (net (code "73") (name "Net-(IC4B-VCC)") (class "Default")
      (node (ref "C25") (pin "1") (pinfunction "1_1") (pintype "passive"))
      (node (ref "IC4") (pin "5") (pinfunction "VCC_5") (pintype "bidirectional"))
      (node (ref "J3") (pin "4") (pinfunction "1_4") (pintype "passive"))
      (node (ref "R21") (pin "1") (pinfunction "1_1") (pintype "passive"))
    )
    (net (code "74") (name "Net-(J1-PS_ON)") (class "Default")
      (node (ref "J1") (pin "16") (pinfunction "PS_ON_16") (pintype "bidirectional"))
      (node (ref "Q1") (pin "3") (pinfunction "C_3") (pintype "bidirectional"))
      (node (ref "R20") (pin "1") (pinfunction "1_1") (pintype "passive"))
    )
    (net (code "75") (name "Net-(J2B-1)") (class "Default")
      (node (ref "D4") (pin "A") (pinfunction "A_A") (pintype "bidirectional"))
      (node (ref "J2") (pin "2") (pinfunction "1_2") (pintype "passive"))
      (node (ref "Q13") (pin "5") (pinfunction "D_5") (pintype "passive"))
      (node (ref "Q13") (pin "6") (pinfunction "D_6") (pintype "passive"))
      (node (ref "Q13") (pin "7") (pinfunction "D_7") (pintype "passive"))
      (node (ref "Q13") (pin "8") (pinfunction "D_8") (pintype "passive"))
    )
    (net (code "76") (name "Net-(J3B-1)") (class "Default")
      (node (ref "D5") (pin "A") (pinfunction "A_A") (pintype "bidirectional"))
      (node (ref "J3") (pin "2") (pinfunction "1_2") (pintype "passive"))
      (node (ref "Q17") (pin "5") (pinfunction "D_5") (pintype "passive"))
      (node (ref "Q17") (pin "6") (pinfunction "D_6") (pintype "passive"))
      (node (ref "Q17") (pin "7") (pinfunction "D_7") (pintype "passive"))
      (node (ref "Q17") (pin "8") (pinfunction "D_8") (pintype "passive"))
    )
    (net (code "77") (name "Net-(J16B-1)") (class "Default")
      (node (ref "D3") (pin "A") (pinfunction "A_A") (pintype "bidirectional"))
      (node (ref "J16") (pin "2") (pinfunction "1_2") (pintype "passive"))
      (node (ref "Q9") (pin "5") (pinfunction "D_5") (pintype "passive"))
      (node (ref "Q9") (pin "6") (pinfunction "D_6") (pintype "passive"))
      (node (ref "Q9") (pin "7") (pinfunction "D_7") (pintype "passive"))
      (node (ref "Q9") (pin "8") (pinfunction "D_8") (pintype "passive"))
    )
    (net (code "78") (name "Net-(Q6-B)") (class "Default")
      (node (ref "Q6") (pin "1") (pinfunction "B_1") (pintype "passive"))
      (node (ref "Q7") (pin "1") (pinfunction "B_1") (pintype "bidirectional"))
      (node (ref "Q8") (pin "3") (pinfunction "C_3") (pintype "bidirectional"))
      (node (ref "R11") (pin "1") (pinfunction "1_1") (pintype "passive"))
    )
    (net (code "79") (name "Net-(Q6-E)") (class "Default")
      (node (ref "Q6") (pin "2") (pinfunction "E_2") (pintype "passive"))
      (node (ref "Q7") (pin "2") (pinfunction "E_2") (pintype "bidirectional"))
      (node (ref "Q9") (pin "4") (pinfunction "G_4") (pintype "passive"))
    )
    (net (code "80") (name "Net-(Q8-B)") (class "Default")
      (node (ref "C19") (pin "1") (pinfunction "1_1") (pintype "passive"))
      (node (ref "Q8") (pin "1") (pinfunction "B_1") (pintype "bidirectional"))
      (node (ref "R12") (pin "1") (pinfunction "1_1") (pintype "passive"))
    )
    (net (code "81") (name "Net-(Q10-B)") (class "Default")
      (node (ref "Q10") (pin "1") (pinfunction "B_1") (pintype "passive"))
      (node (ref "Q11") (pin "1") (pinfunction "B_1") (pintype "bidirectional"))
      (node (ref "Q12") (pin "3") (pinfunction "C_3") (pintype "bidirectional"))
      (node (ref "R16") (pin "1") (pinfunction "1_1") (pintype "passive"))
    )
    (net (code "82") (name "Net-(Q10-E)") (class "Default")
      (node (ref "Q10") (pin "2") (pinfunction "E_2") (pintype "passive"))
      (node (ref "Q11") (pin "2") (pinfunction "E_2") (pintype "bidirectional"))
      (node (ref "Q13") (pin "4") (pinfunction "G_4") (pintype "passive"))
    )
    (net (code "83") (name "Net-(Q12-B)") (class "Default")
      (node (ref "C22") (pin "1") (pinfunction "1_1") (pintype "passive"))
      (node (ref "Q12") (pin "1") (pinfunction "B_1") (pintype "bidirectional"))
      (node (ref "R18") (pin "1") (pinfunction "1_1") (pintype "passive"))
    )
    (net (code "84") (name "Net-(Q14-B)") (class "Default")
      (node (ref "Q14") (pin "1") (pinfunction "B_1") (pintype "passive"))
      (node (ref "Q15") (pin "1") (pinfunction "B_1") (pintype "bidirectional"))
      (node (ref "Q16") (pin "3") (pinfunction "C_3") (pintype "bidirectional"))
      (node (ref "R24") (pin "1") (pinfunction "1_1") (pintype "passive"))
    )
    (net (code "85") (name "Net-(Q14-E)") (class "Default")
      (node (ref "Q14") (pin "2") (pinfunction "E_2") (pintype "passive"))
      (node (ref "Q15") (pin "2") (pinfunction "E_2") (pintype "bidirectional"))
      (node (ref "Q17") (pin "4") (pinfunction "G_4") (pintype "passive"))
    )
    (net (code "86") (name "Net-(Q16-B)") (class "Default")
      (node (ref "C27") (pin "1") (pinfunction "1_1") (pintype "passive"))
      (node (ref "Q16") (pin "1") (pinfunction "B_1") (pintype "bidirectional"))
      (node (ref "R25") (pin "1") (pinfunction "1_1") (pintype "passive"))
    )
    (net (code "87") (name "Net-(R26-PadR2A)") (class "Default")
      (node (ref "R26") (pin "R2A") (pinfunction "R2A_R2A") (pintype "passive"))
      (node (ref "U1") (pin "BLUE") (pinfunction "BLUE_BLUE") (pintype "bidirectional"))
    )
    (net (code "88") (name "Net-(R26-PadR3A)") (class "Default")
      (node (ref "R26") (pin "R3A") (pinfunction "R3A_R3A") (pintype "passive"))
      (node (ref "U1") (pin "GRN") (pinfunction "GRN_GRN") (pintype "bidirectional"))
    )
    (net (code "89") (name "Net-(R26-PadR4A)") (class "Default")
      (node (ref "R26") (pin "R4A") (pinfunction "R4A_R4A") (pintype "passive"))
      (node (ref "U1") (pin "RED") (pinfunction "RED_RED") (pintype "bidirectional"))
    )
    (net (code "90") (name "Net-(U3-RC12{slash}OSC1)") (class "Default")
      (node (ref "C2") (pin "1") (pinfunction "1_1") (pintype "passive"))
      (node (ref "U3") (pin "P$39") (pinfunction "RC12/OSC1_P$39") (pintype "bidirectional"))
      (node (ref "X2") (pin "P$1") (pinfunction "P$1_P$1") (pintype "bidirectional"))
    )
    (net (code "91") (name "Net-(U3-RC15{slash}OSC2)") (class "Default")
      (node (ref "C3") (pin "1") (pinfunction "1_1") (pintype "passive"))
      (node (ref "U3") (pin "P$40") (pinfunction "RC15/OSC2_P$40") (pintype "bidirectional"))
      (node (ref "X2") (pin "P$3") (pinfunction "P$2_P$3") (pintype "bidirectional"))
    )
    (net (code "92") (name "Net-(U3-VCAP)") (class "Default")
      (node (ref "C10") (pin "+") (pinfunction "+_+") (pintype "passive"))
      (node (ref "C11") (pin "1") (pinfunction "1_1") (pintype "passive"))
      (node (ref "U3") (pin "P$56") (pinfunction "VCAP_P$56") (pintype "bidirectional"))
    )
    (net (code "93") (name "Net-(U18-BYPASS)") (class "Default")
      (node (ref "C9") (pin "1") (pinfunction "1_1") (pintype "passive"))
      (node (ref "U18") (pin "4") (pinfunction "BYPASS_4") (pintype "bidirectional"))
    )
    (net (code "94") (name "Net-(U18-EN)") (class "Default")
      (node (ref "R4") (pin "2") (pinfunction "2_2") (pintype "passive"))
      (node (ref "U18") (pin "3") (pinfunction "EN_3") (pintype "bidirectional"))
    )
    (net (code "95") (name "unconnected-(J1--12V-Pad14)") (class "Default")
      (node (ref "J1") (pin "14") (pinfunction "-12V_14") (pintype "bidirectional"))
    )
    (net (code "96") (name "unconnected-(J1-NC-Pad20)") (class "Default")
      (node (ref "J1") (pin "20") (pinfunction "NC_20") (pintype "bidirectional"))
    )
    (net (code "97") (name "unconnected-(J1-PWR_OK-Pad8)") (class "Default")
      (node (ref "J1") (pin "8") (pinfunction "PWR_OK_8") (pintype "bidirectional"))
    )
    (net (code "98") (name "unconnected-(J10-PadCTS)") (class "Default")
      (node (ref "J10") (pin "CTS") (pinfunction "CTS_CTS") (pintype "bidirectional"))
    )
    (net (code "99") (name "unconnected-(J10-PadRTS)") (class "Default")
      (node (ref "J10") (pin "RTS") (pinfunction "RTS_RTS") (pintype "bidirectional"))
    )
    (net (code "100") (name "unconnected-(R19-PadR1A)") (class "Default")
      (node (ref "R19") (pin "R1A") (pinfunction "R1A_R1A") (pintype "passive"))
    )
    (net (code "101") (name "unconnected-(R19-PadR4A)") (class "Default")
      (node (ref "R19") (pin "R4A") (pinfunction "R4A_R4A") (pintype "passive"))
    )
    (net (code "102") (name "unconnected-(R26-PadR1A)") (class "Default")
      (node (ref "R26") (pin "R1A") (pinfunction "R1A_R1A") (pintype "passive"))
    )
    (net (code "103") (name "unconnected-(R26-PadR1B)") (class "Default")
      (node (ref "R26") (pin "R1B") (pinfunction "R1B_R1B") (pintype "passive"))
    )
    (net (code "104") (name "unconnected-(U$1-5-PadP$5)") (class "Default")
      (node (ref "U$1") (pin "P$5") (pinfunction "5_P$5") (pintype "bidirectional"))
    )
    (net (code "105") (name "unconnected-(U$1-6-PadP$6)") (class "Default")
      (node (ref "U$1") (pin "P$6") (pinfunction "6_P$6") (pintype "bidirectional"))
    )
    (net (code "106") (name "unconnected-(U$2-5-PadP$5)") (class "Default")
      (node (ref "U$2") (pin "P$5") (pinfunction "5_P$5") (pintype "bidirectional"))
    )
    (net (code "107") (name "unconnected-(U$2-6-PadP$6)") (class "Default")
      (node (ref "U$2") (pin "P$6") (pinfunction "6_P$6") (pintype "bidirectional"))
    )
    (net (code "108") (name "unconnected-(U$3-5-PadP$5)") (class "Default")
      (node (ref "U$3") (pin "P$5") (pinfunction "5_P$5") (pintype "bidirectional"))
    )
    (net (code "109") (name "unconnected-(U$3-6-PadP$6)") (class "Default")
      (node (ref "U$3") (pin "P$6") (pinfunction "6_P$6") (pintype "bidirectional"))
    )
    (net (code "110") (name "unconnected-(U$4-5-PadP$5)") (class "Default")
      (node (ref "U$4") (pin "P$5") (pinfunction "5_P$5") (pintype "bidirectional"))
    )
    (net (code "111") (name "unconnected-(U$4-6-PadP$6)") (class "Default")
      (node (ref "U$4") (pin "P$6") (pinfunction "6_P$6") (pintype "bidirectional"))
    )
    (net (code "112") (name "unconnected-(U$5-5-PadP$5)") (class "Default")
      (node (ref "U$5") (pin "P$5") (pinfunction "5_P$5") (pintype "bidirectional"))
    )
    (net (code "113") (name "unconnected-(U$5-6-PadP$6)") (class "Default")
      (node (ref "U$5") (pin "P$6") (pinfunction "6_P$6") (pintype "bidirectional"))
    )
    (net (code "114") (name "unconnected-(U$6-5-PadP$5)") (class "Default")
      (node (ref "U$6") (pin "P$5") (pinfunction "5_P$5") (pintype "bidirectional"))
    )
    (net (code "115") (name "unconnected-(U$6-6-PadP$6)") (class "Default")
      (node (ref "U$6") (pin "P$6") (pinfunction "6_P$6") (pintype "bidirectional"))
    )
    (net (code "116") (name "unconnected-(U$7-5-PadP$5)") (class "Default")
      (node (ref "U$7") (pin "P$5") (pinfunction "5_P$5") (pintype "bidirectional"))
    )
    (net (code "117") (name "unconnected-(U$7-6-PadP$6)") (class "Default")
      (node (ref "U$7") (pin "P$6") (pinfunction "6_P$6") (pintype "bidirectional"))
    )
    (net (code "118") (name "unconnected-(U$8-5-PadP$5)") (class "Default")
      (node (ref "U$8") (pin "P$5") (pinfunction "5_P$5") (pintype "bidirectional"))
    )
    (net (code "119") (name "unconnected-(U$8-6-PadP$6)") (class "Default")
      (node (ref "U$8") (pin "P$6") (pinfunction "6_P$6") (pintype "bidirectional"))
    )
    (net (code "120") (name "unconnected-(U3-RC13-PadP$47)") (class "Default")
      (node (ref "U3") (pin "P$47") (pinfunction "RC13_P$47") (pintype "bidirectional"))
    )
    (net (code "121") (name "unconnected-(U3-RC14-PadP$48)") (class "Default")
      (node (ref "U3") (pin "P$48") (pinfunction "RC14_P$48") (pintype "bidirectional"))
    )
    (net (code "122") (name "unconnected-(U3-RD1{slash}OC2-PadP$49)") (class "Default")
      (node (ref "U3") (pin "P$49") (pinfunction "RD1/OC2_P$49") (pintype "bidirectional"))
    )
    (net (code "123") (name "unconnected-(U3-RD8-PadP$42)") (class "Default")
      (node (ref "U3") (pin "P$42") (pinfunction "RD8_P$42") (pintype "bidirectional"))
    )
    (net (code "124") (name "unconnected-(U3-RD9-PadP$43)") (class "Default")
      (node (ref "U3") (pin "P$43") (pinfunction "RD9_P$43") (pintype "bidirectional"))
    )
    (net (code "125") (name "unconnected-(U3-RF4{slash}U2RX-PadP$31)") (class "Default")
      (node (ref "U3") (pin "P$31") (pinfunction "RF4/U2RX_P$31") (pintype "bidirectional"))
    )
    (net (code "126") (name "unconnected-(U25-PadP1)") (class "Default")
      (node (ref "U25") (pin "P1") (pinfunction "P1_P1") (pintype "bidirectional"))
    )
    (net (code "127") (name "unconnected-(U25-PadP2)") (class "Default")
      (node (ref "U25") (pin "P2") (pinfunction "P2_P2") (pintype "bidirectional"))
    )
    (net (code "128") (name "unconnected-(U25-PadP3)") (class "Default")
      (node (ref "U25") (pin "P3") (pinfunction "P3_P3") (pintype "bidirectional"))
    )
    (net (code "129") (name "unconnected-(U25-PadP4)") (class "Default")
      (node (ref "U25") (pin "P4") (pinfunction "P4_P4") (pintype "bidirectional"))
    )
    (net (code "130") (name "unconnected-(X1F-S-Pad6)") (class "Default")
      (node (ref "X1") (pin "6") (pinfunction "S_6") (pintype "passive"))
    )
    (net (code "131") (name "unconnected-(X2-SHIELD-PadP$4)") (class "Default")
      (node (ref "X2") (pin "P$4") (pinfunction "SHIELD_P$4") (pintype "bidirectional"))
    )
  )
)
